# Top_Layer.net
KiCad netlist of a schematic drawn in Altium Designer
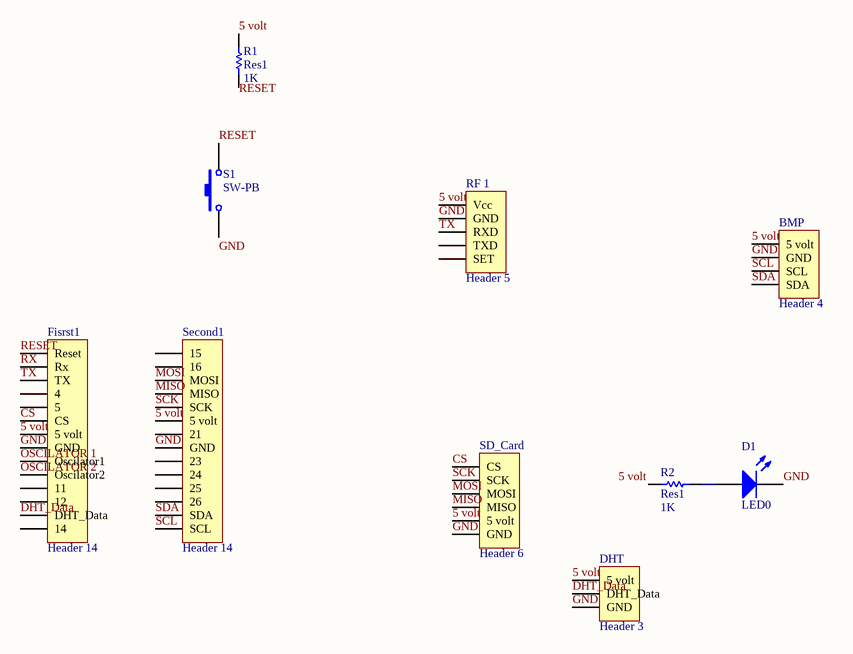
[diagram p0: Top Layer.SchDoc]

(export (version "E")
  (design (tool "Eeschema 10.0.6"))
  (components
    (comp (ref "BMP")
      (value "Header 4")
      (footprint "HDR1X4")
      (description "Header, 4-Pin")
      (fields (field (name "PUBLISHER") "Altium Limited"))
      (libsource (lib "Miscellaneous Connectors") (part "Header 4"))
    )
    (comp (ref "D1")
      (value "LED0")
      (footprint "LED-0")
      (description "Typical INFRARED GaAs LED")
      (fields (field (name "PUBLISHER") "Altium Limited"))
      (libsource (lib "Miscellaneous Devices") (part "LED0"))
    )
    (comp (ref "DHT")
      (value "Header 3")
      (footprint "HDR1X3")
      (description "Header, 3-Pin")
      (fields (field (name "PUBLISHER") "Altium Limited"))
      (libsource (lib "Miscellaneous Connectors") (part "Header 3"))
    )
    (comp (ref "Fisrst1")
      (value "Header 14")
      (footprint "HDR1X14")
      (description "Header, 14-Pin")
      (fields (field (name "PUBLISHER") "Altium Limited"))
      (libsource (lib "Miscellaneous Connectors") (part "Header 14"))
    )
    (comp (ref "R1")
      (value "Res1")
      (footprint "AXIAL-0.3")
      (description "Resistor")
      (fields (field (name "ALTIUM_VALUE") "1K") (field (name "PUBLISHER") "Altium Limited"))
      (libsource (lib "Miscellaneous Devices") (part "Res1"))
    )
    (comp (ref "R2")
      (value "Res1")
      (footprint "AXIAL-0.3")
      (description "Resistor")
      (fields (field (name "ALTIUM_VALUE") "1K") (field (name "PUBLISHER") "Altium Limited"))
      (libsource (lib "Miscellaneous Devices") (part "Res1"))
    )
    (comp (ref "RF 1")
      (value "Header 5")
      (footprint "HDR1X5")
      (description "Header, 5-Pin")
      (fields (field (name "PUBLISHER") "Altium Limited"))
      (libsource (lib "Miscellaneous Connectors") (part "Header 5"))
    )
    (comp (ref "S1")
      (value "SW-PB")
      (footprint "SPST-2")
      (description "Switch")
      (fields (field (name "PUBLISHER") "Altium Limited"))
      (libsource (lib "Miscellaneous Devices") (part "SW-PB"))
    )
    (comp (ref "SD_Card")
      (value "Header 6")
      (footprint "HDR1X6")
      (description "Header, 6-Pin")
      (fields (field (name "PUBLISHER") "Altium Limited"))
      (libsource (lib "Miscellaneous Connectors") (part "Header 6"))
    )
    (comp (ref "Second1")
      (value "Header 14")
      (footprint "HDR1X14")
      (description "Header, 14-Pin")
      (fields (field (name "PUBLISHER") "Altium Limited"))
      (libsource (lib "Miscellaneous Connectors") (part "Header 14"))
    )
  )
  (nets
    (net (code "1") (name "/5 volt") (class "Default")
      (node (ref "BMP") (pin "1") (pinfunction "5_volt_1") (pintype "passive"))
      (node (ref "DHT") (pin "1") (pinfunction "5_volt_1") (pintype "passive"))
      (node (ref "Fisrst1") (pin "7") (pinfunction "5_volt_7") (pintype "passive"))
      (node (ref "R1") (pin "2") (pinfunction "2_2") (pintype "passive"))
      (node (ref "R2") (pin "1") (pinfunction "1_1") (pintype "passive"))
      (node (ref "RF 1") (pin "1") (pinfunction "Vcc_1") (pintype "passive"))
      (node (ref "SD_Card") (pin "5") (pinfunction "5_volt_5") (pintype "passive"))
      (node (ref "Second1") (pin "6") (pinfunction "CS_6") (pintype "passive"))
    )
    (net (code "2") (name "/CS") (class "Default")
      (node (ref "Fisrst1") (pin "6") (pinfunction "CS_6") (pintype "passive"))
      (node (ref "SD_Card") (pin "1") (pinfunction "CS_1") (pintype "passive"))
    )
    (net (code "3") (name "/DHT_Data") (class "Default")
      (node (ref "DHT") (pin "2") (pinfunction "DHT_Data_2") (pintype "passive"))
      (node (ref "Fisrst1") (pin "13") (pinfunction "DHT_Data_13") (pintype "passive"))
    )
    (net (code "4") (name "/GND") (class "Default")
      (node (ref "BMP") (pin "2") (pinfunction "GND_2") (pintype "passive"))
      (node (ref "D1") (pin "2") (pinfunction "K_2") (pintype "passive"))
      (node (ref "DHT") (pin "3") (pinfunction "GND_3") (pintype "passive"))
      (node (ref "Fisrst1") (pin "8") (pinfunction "GND_8") (pintype "passive"))
      (node (ref "RF 1") (pin "2") (pinfunction "GND_2") (pintype "passive"))
      (node (ref "S1") (pin "1") (pinfunction "1_1") (pintype "passive"))
      (node (ref "SD_Card") (pin "6") (pinfunction "GND_6") (pintype "passive"))
      (node (ref "Second1") (pin "8") (pinfunction "GND_8") (pintype "passive"))
    )
    (net (code "5") (name "/MISO") (class "Default")
      (node (ref "SD_Card") (pin "4") (pinfunction "MISO_4") (pintype "passive"))
      (node (ref "Second1") (pin "4") (pinfunction "4_4") (pintype "passive"))
    )
    (net (code "6") (name "/MOSI") (class "Default")
      (node (ref "SD_Card") (pin "3") (pinfunction "MOSI_3") (pintype "passive"))
      (node (ref "Second1") (pin "3") (pinfunction "TX_3") (pintype "passive"))
    )
    (net (code "7") (name "/OSCILATOR 1") (class "Default")
      (node (ref "Fisrst1") (pin "9") (pinfunction "Oscilator1_9") (pintype "passive"))
    )
    (net (code "8") (name "/OSCILATOR 2") (class "Default")
      (node (ref "Fisrst1") (pin "10") (pinfunction "Oscilator2_10") (pintype "passive"))
    )
    (net (code "9") (name "/RESET") (class "Default")
      (node (ref "Fisrst1") (pin "1") (pinfunction "Reset_1") (pintype "passive"))
      (node (ref "R1") (pin "1") (pinfunction "1_1") (pintype "passive"))
      (node (ref "S1") (pin "2") (pinfunction "2_2") (pintype "passive"))
    )
    (net (code "10") (name "/RX") (class "Default")
      (node (ref "Fisrst1") (pin "2") (pinfunction "Rx_2") (pintype "passive"))
    )
    (net (code "11") (name "/SCK") (class "Default")
      (node (ref "SD_Card") (pin "2") (pinfunction "SCK_2") (pintype "passive"))
      (node (ref "Second1") (pin "5") (pinfunction "5_5") (pintype "passive"))
    )
    (net (code "12") (name "/SCL") (class "Default")
      (node (ref "BMP") (pin "3") (pinfunction "SCL_3") (pintype "passive"))
      (node (ref "Second1") (pin "14") (pinfunction "14_14") (pintype "passive"))
    )
    (net (code "13") (name "/SDA") (class "Default")
      (node (ref "BMP") (pin "4") (pinfunction "SDA_4") (pintype "passive"))
      (node (ref "Second1") (pin "13") (pinfunction "DHT_Data_13") (pintype "passive"))
    )
    (net (code "14") (name "/TX") (class "Default")
      (node (ref "Fisrst1") (pin "3") (pinfunction "TX_3") (pintype "passive"))
      (node (ref "RF 1") (pin "3") (pinfunction "RXD_3") (pintype "passive"))
    )
    (net (code "15") (name "Net-(D1-A)") (class "Default")
      (node (ref "D1") (pin "1") (pinfunction "A_1") (pintype "passive"))
      (node (ref "R2") (pin "2") (pinfunction "2_2") (pintype "passive"))
    )
    (net (code "16") (name "unconnected-(Fisrst1-Pad4)") (class "Default")
      (node (ref "Fisrst1") (pin "4") (pinfunction "4_4") (pintype "passive"))
    )
    (net (code "17") (name "unconnected-(Fisrst1-Pad5)") (class "Default")
      (node (ref "Fisrst1") (pin "5") (pinfunction "5_5") (pintype "passive"))
    )
    (net (code "18") (name "unconnected-(Fisrst1-Pad11)") (class "Default")
      (node (ref "Fisrst1") (pin "11") (pinfunction "11_11") (pintype "passive"))
    )
    (net (code "19") (name "unconnected-(Fisrst1-Pad12)") (class "Default")
      (node (ref "Fisrst1") (pin "12") (pinfunction "12_12") (pintype "passive"))
    )
    (net (code "20") (name "unconnected-(Fisrst1-Pad14)") (class "Default")
      (node (ref "Fisrst1") (pin "14") (pinfunction "14_14") (pintype "passive"))
    )
    (net (code "21") (name "unconnected-(RF 1-SET-Pad5)") (class "Default")
      (node (ref "RF 1") (pin "5") (pinfunction "SET_5") (pintype "passive"))
    )
    (net (code "22") (name "unconnected-(RF 1-TXD-Pad4)") (class "Default")
      (node (ref "RF 1") (pin "4") (pinfunction "TXD_4") (pintype "passive"))
    )
    (net (code "23") (name "unconnected-(Second1-5_volt-Pad7)") (class "Default")
      (node (ref "Second1") (pin "7") (pinfunction "5_volt_7") (pintype "passive"))
    )
    (net (code "24") (name "unconnected-(Second1-Oscilator1-Pad9)") (class "Default")
      (node (ref "Second1") (pin "9") (pinfunction "Oscilator1_9") (pintype "passive"))
    )
    (net (code "25") (name "unconnected-(Second1-Oscilator2-Pad10)") (class "Default")
      (node (ref "Second1") (pin "10") (pinfunction "Oscilator2_10") (pintype "passive"))
    )
    (net (code "26") (name "unconnected-(Second1-Pad11)") (class "Default")
      (node (ref "Second1") (pin "11") (pinfunction "11_11") (pintype "passive"))
    )
    (net (code "27") (name "unconnected-(Second1-Pad12)") (class "Default")
      (node (ref "Second1") (pin "12") (pinfunction "12_12") (pintype "passive"))
    )
    (net (code "28") (name "unconnected-(Second1-Reset-Pad1)") (class "Default")
      (node (ref "Second1") (pin "1") (pinfunction "Reset_1") (pintype "passive"))
    )
    (net (code "29") (name "unconnected-(Second1-Rx-Pad2)") (class "Default")
      (node (ref "Second1") (pin "2") (pinfunction "Rx_2") (pintype "passive"))
    )
  )
)
